# 2022-4T-MNT-2.net
KiCad netlist of a schematic drawn in EasyEDA Pro
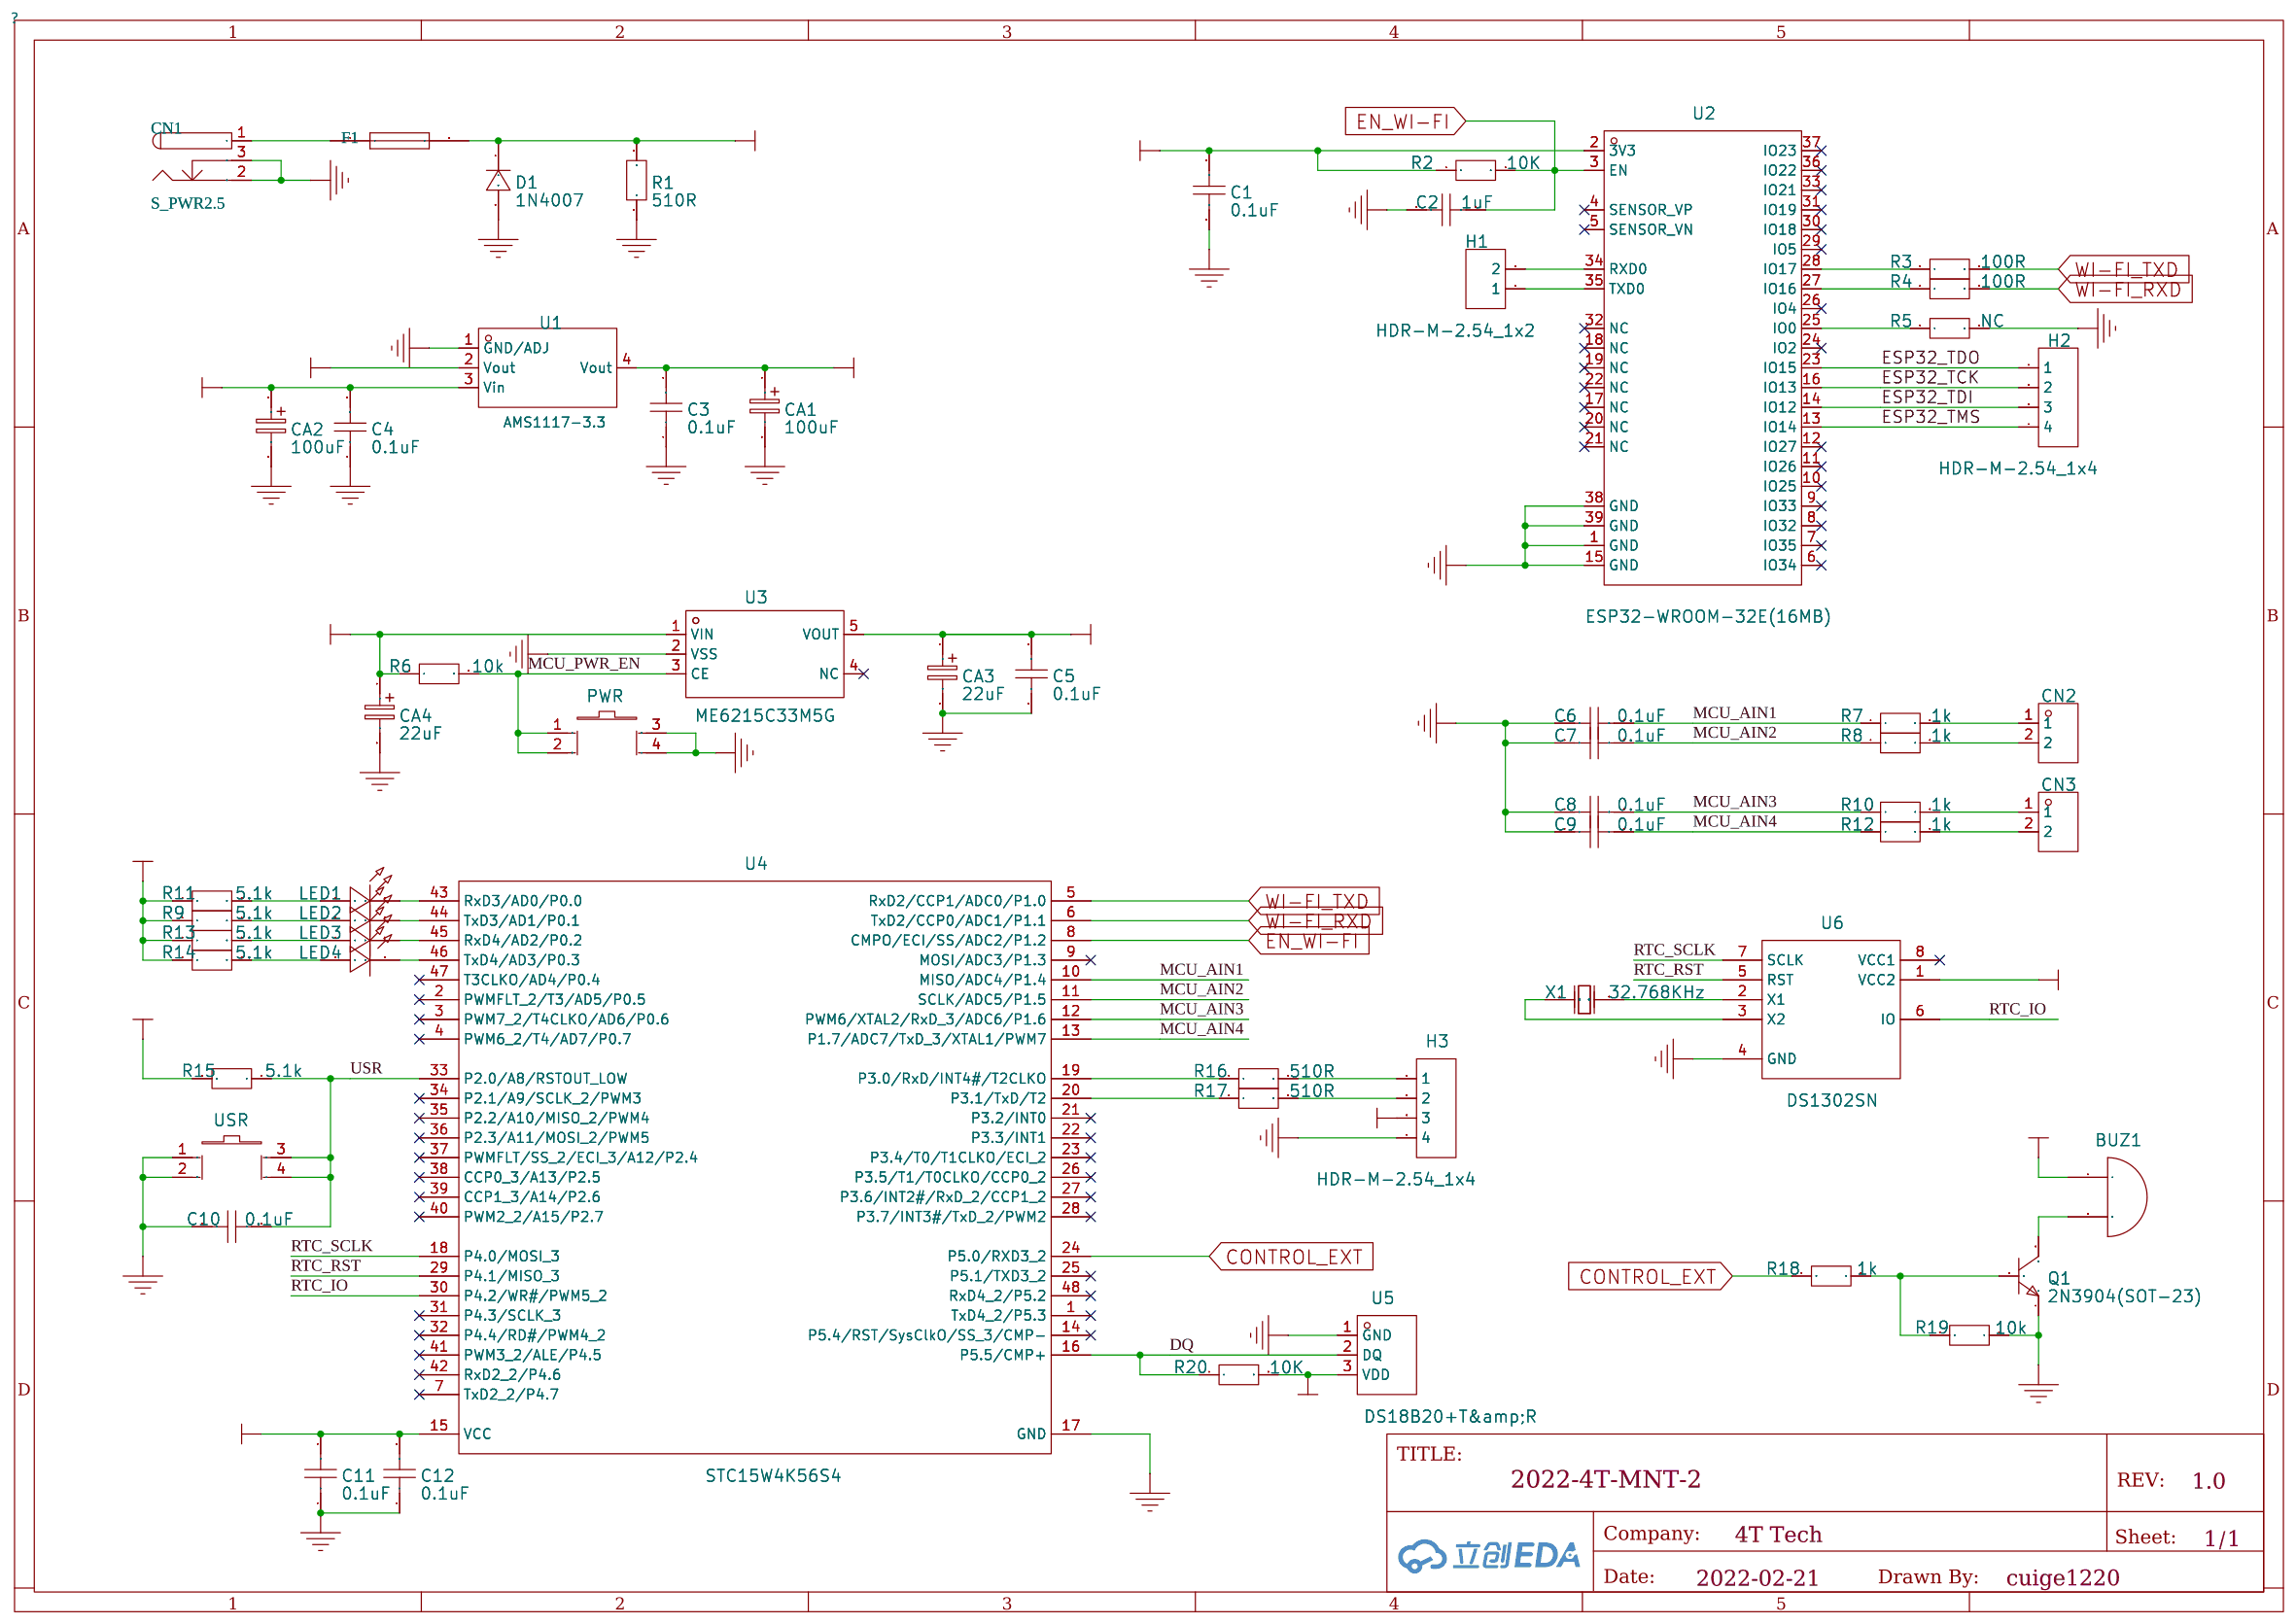
[diagram p0: schematic sheet]

(export (version "E")
  (design (tool "Eeschema 10.0.6"))
  (components
    (comp (ref "BUZ1") (value "BUZ1") (libsource (lib "easyedapro") (part "BUZ1")))
    (comp (ref "C1") (value "0.1uF") (libsource (lib "easyedapro") (part "0.1uF")))
    (comp (ref "C2") (value "1uF") (libsource (lib "easyedapro") (part "1uF")))
    (comp (ref "C3") (value "0.1uF") (libsource (lib "easyedapro") (part "0.1uF")))
    (comp (ref "C4") (value "0.1uF") (libsource (lib "easyedapro") (part "0.1uF")))
    (comp (ref "C5") (value "0.1uF") (libsource (lib "easyedapro") (part "0.1uF")))
    (comp (ref "C6") (value "0.1uF") (libsource (lib "easyedapro") (part "0.1uF")))
    (comp (ref "C7") (value "0.1uF") (libsource (lib "easyedapro") (part "0.1uF")))
    (comp (ref "C8") (value "0.1uF") (libsource (lib "easyedapro") (part "0.1uF")))
    (comp (ref "C9") (value "0.1uF") (libsource (lib "easyedapro") (part "0.1uF")))
    (comp (ref "C10") (value "0.1uF") (libsource (lib "easyedapro") (part "0.1uF")))
    (comp (ref "C11") (value "0.1uF") (libsource (lib "easyedapro") (part "0.1uF")))
    (comp (ref "C12") (value "0.1uF") (libsource (lib "easyedapro") (part "0.1uF")))
    (comp (ref "CA1") (value "100uF") (libsource (lib "easyedapro") (part "100uF")))
    (comp (ref "CA2") (value "100uF") (libsource (lib "easyedapro") (part "100uF")))
    (comp (ref "CA3") (value "22uF") (libsource (lib "easyedapro") (part "22uF")))
    (comp (ref "CA4") (value "22uF") (libsource (lib "easyedapro") (part "22uF")))
    (comp (ref "CN1") (value "S_PWR2.5") (libsource (lib "easyedapro") (part "S_PWR2.5")))
    (comp (ref "CN2")
      (value "DB128L-5.08-2P")
      (fields (field (name "Manufacturer") "DIBO"))
      (libsource (lib "easyedapro") (part "DB128L-5.08-2P"))
    )
    (comp (ref "CN3")
      (value "DB128L-5.08-2P")
      (fields (field (name "Manufacturer") "DIBO"))
      (libsource (lib "easyedapro") (part "DB128L-5.08-2P"))
    )
    (comp (ref "D1")
      (value "1N4007")
      (fields (field (name "Manufacturer") "SEMTECH"))
      (libsource (lib "easyedapro") (part "1N4007"))
    )
    (comp (ref "F1")
      (value "ASMD1210-075")
      (fields (field (name "Publisher") "Altium Limited"))
      (libsource (lib "easyedapro") (part "ASMD1210-075"))
    )
    (comp (ref "H1") (value "HDR-M-2.54_1x2") (libsource (lib "easyedapro") (part "HDR-M-2.54_1x2")))
    (comp (ref "H2") (value "HDR-M-2.54_1x4") (libsource (lib "easyedapro") (part "HDR-M-2.54_1x4")))
    (comp (ref "H3") (value "HDR-M-2.54_1x4") (libsource (lib "easyedapro") (part "HDR-M-2.54_1x4")))
    (comp (ref "LED1")
      (value "LED-TH-3mm_R")
      (fields
        (field (name "Manufacturer Part") "204-10SDRD/S530-A3-L")
        (field (name "Manufacturer") "EVERLIGHT(台湾亿光)")
      )
      (libsource (lib "easyedapro") (part "LED-TH-3mm_R"))
    )
    (comp (ref "LED2")
      (value "LED-TH-3mm_R")
      (fields
        (field (name "Manufacturer Part") "204-10SDRD/S530-A3-L")
        (field (name "Manufacturer") "EVERLIGHT(台湾亿光)")
      )
      (libsource (lib "easyedapro") (part "LED-TH-3mm_R"))
    )
    (comp (ref "LED3")
      (value "LED-TH-3mm_R")
      (fields
        (field (name "Manufacturer Part") "204-10SDRD/S530-A3-L")
        (field (name "Manufacturer") "EVERLIGHT(台湾亿光)")
      )
      (libsource (lib "easyedapro") (part "LED-TH-3mm_R"))
    )
    (comp (ref "LED4")
      (value "LED-TH-3mm_R")
      (fields
        (field (name "Manufacturer Part") "204-10SDRD/S530-A3-L")
        (field (name "Manufacturer") "EVERLIGHT(台湾亿光)")
      )
      (libsource (lib "easyedapro") (part "LED-TH-3mm_R"))
    )
    (comp (ref "PWR")
      (value "6x6x6Plastic head")
      (fields (field (name "Manufacturer") "ReliaPro"))
      (libsource (lib "easyedapro") (part "6x6x6Plastic head"))
    )
    (comp (ref "Q1")
      (value "2N3904(SOT-23)")
      (fields (field (name "Manufacturer Part") "2n3904S-RTK/PS") (field (name "Manufacturer") "KEC"))
      (libsource (lib "easyedapro") (part "2N3904(SOT-23)"))
    )
    (comp (ref "R1") (value "510R") (libsource (lib "easyedapro") (part "510R")))
    (comp (ref "R2") (value "10K") (libsource (lib "easyedapro") (part "10K")))
    (comp (ref "R3") (value "100R") (libsource (lib "easyedapro") (part "100R")))
    (comp (ref "R4") (value "100R") (libsource (lib "easyedapro") (part "100R")))
    (comp (ref "R5") (value "NC") (libsource (lib "easyedapro") (part "NC")))
    (comp (ref "R6") (value "10k") (libsource (lib "easyedapro") (part "10k")))
    (comp (ref "R7") (value "1k") (libsource (lib "easyedapro") (part "1k")))
    (comp (ref "R8") (value "1k") (libsource (lib "easyedapro") (part "1k")))
    (comp (ref "R9") (value "5.1k") (libsource (lib "easyedapro") (part "5.1k")))
    (comp (ref "R10") (value "1k") (libsource (lib "easyedapro") (part "1k")))
    (comp (ref "R11") (value "5.1k") (libsource (lib "easyedapro") (part "5.1k")))
    (comp (ref "R12") (value "1k") (libsource (lib "easyedapro") (part "1k")))
    (comp (ref "R13") (value "5.1k") (libsource (lib "easyedapro") (part "5.1k")))
    (comp (ref "R14") (value "5.1k") (libsource (lib "easyedapro") (part "5.1k")))
    (comp (ref "R15") (value "5.1k") (libsource (lib "easyedapro") (part "5.1k")))
    (comp (ref "R16") (value "510R") (libsource (lib "easyedapro") (part "510R")))
    (comp (ref "R17") (value "510R") (libsource (lib "easyedapro") (part "510R")))
    (comp (ref "R18") (value "1k") (libsource (lib "easyedapro") (part "1k")))
    (comp (ref "R19") (value "10k") (libsource (lib "easyedapro") (part "10k")))
    (comp (ref "R20") (value "10K") (libsource (lib "easyedapro") (part "10K")))
    (comp (ref "U1")
      (value "AMS1117-3.3")
      (fields (field (name "Manufacturer") "AMS"))
      (libsource (lib "easyedapro") (part "AMS1117-3.3"))
    )
    (comp (ref "U2")
      (value "ESP32-WROOM-32E(16MB)")
      (fields (field (name "Manufacturer") "Espressif Systems"))
      (libsource (lib "easyedapro") (part "ESP32-WROOM-32E(16MB)"))
    )
    (comp (ref "U3")
      (value "ME6215C33M5G")
      (fields (field (name "Manufacturer") "MICRONE"))
      (libsource (lib "easyedapro") (part "ME6215C33M5G"))
    )
    (comp (ref "U4")
      (value "STC15W4K56S4")
      (fields (field (name "Manufacturer") "STC"))
      (libsource (lib "easyedapro") (part "STC15W4K56S4"))
    )
    (comp (ref "U5")
      (value "DS18B20+T&amp;R")
      (fields (field (name "Manufacturer") "MAXIM(美信)"))
      (libsource (lib "easyedapro") (part "DS18B20+T&amp;R"))
    )
    (comp (ref "U6") (value "DS1302SN") (libsource (lib "easyedapro") (part "DS1302SN")))
    (comp (ref "USR")
      (value "6x6x6Plastic head")
      (fields (field (name "Manufacturer") "ReliaPro"))
      (libsource (lib "easyedapro") (part "6x6x6Plastic head"))
    )
    (comp (ref "X1")
      (value "32.768KHz")
      (fields (field (name "Manufacturer Part") "CFS-20632768EZFB") (field (name "Manufacturer") "CITIZEN"))
      (libsource (lib "easyedapro") (part "32.768KHz"))
    )
  )
  (nets
    (net (code "1") (name "+5V0") (class "Default")
      (node (ref "C4") (pin "2") (pinfunction "2_2") (pintype "input"))
      (node (ref "CA2") (pin "1") (pinfunction "1_1") (pintype "input"))
      (node (ref "CA4") (pin "1") (pinfunction "1_1") (pintype "input"))
      (node (ref "D1") (pin "1") (pinfunction "1_1") (pintype "input"))
      (node (ref "F1") (pin "2") (pinfunction "2_2") (pintype "input"))
      (node (ref "R1") (pin "2") (pinfunction "2_2") (pintype "input"))
      (node (ref "R6") (pin "1") (pinfunction "1_1") (pintype "input"))
      (node (ref "U1") (pin "3") (pinfunction "Vin_3") (pintype "input"))
      (node (ref "U3") (pin "1") (pinfunction "VIN_1") (pintype "input"))
    )
    (net (code "2") (name "/DQ") (class "Default")
      (node (ref "R20") (pin "1") (pinfunction "1_1") (pintype "input"))
      (node (ref "U4") (pin "16") (pinfunction "P5.5/CMP+_16") (pintype "input"))
      (node (ref "U5") (pin "2") (pinfunction "DQ_2") (pintype "input"))
    )
    (net (code "3") (name "/ESP32_TCK") (class "Default")
      (node (ref "H2") (pin "2") (pinfunction "2_2") (pintype "input"))
      (node (ref "U2") (pin "16") (pinfunction "IO13_16") (pintype "input"))
    )
    (net (code "4") (name "/ESP32_TDI") (class "Default")
      (node (ref "H2") (pin "3") (pinfunction "3_3") (pintype "input"))
      (node (ref "U2") (pin "14") (pinfunction "IO12_14") (pintype "input"))
    )
    (net (code "5") (name "/ESP32_TDO") (class "Default")
      (node (ref "H2") (pin "1") (pinfunction "1_1") (pintype "input"))
      (node (ref "U2") (pin "23") (pinfunction "IO15_23") (pintype "input"))
    )
    (net (code "6") (name "/ESP32_TMS") (class "Default")
      (node (ref "H2") (pin "4") (pinfunction "4_4") (pintype "input"))
      (node (ref "U2") (pin "13") (pinfunction "IO14_13") (pintype "input"))
    )
    (net (code "7") (name "/MCU_AIN1") (class "Default")
      (node (ref "C6") (pin "2") (pinfunction "2_2") (pintype "input"))
      (node (ref "R7") (pin "1") (pinfunction "1_1") (pintype "input"))
      (node (ref "U4") (pin "10") (pinfunction "MISO/ADC4/P1.4_10") (pintype "input"))
    )
    (net (code "8") (name "/MCU_AIN2") (class "Default")
      (node (ref "C7") (pin "2") (pinfunction "2_2") (pintype "input"))
      (node (ref "R8") (pin "1") (pinfunction "1_1") (pintype "input"))
      (node (ref "U4") (pin "11") (pinfunction "SCLK/ADC5/P1.5_11") (pintype "input"))
    )
    (net (code "9") (name "/MCU_AIN3") (class "Default")
      (node (ref "C8") (pin "2") (pinfunction "2_2") (pintype "input"))
      (node (ref "R10") (pin "1") (pinfunction "1_1") (pintype "input"))
      (node (ref "U4") (pin "12") (pinfunction "PWM6/XTAL2/RxD_3/ADC6/P1.6_12") (pintype "input"))
    )
    (net (code "10") (name "/MCU_AIN4") (class "Default")
      (node (ref "C9") (pin "2") (pinfunction "2_2") (pintype "input"))
      (node (ref "R12") (pin "1") (pinfunction "1_1") (pintype "input"))
      (node (ref "U4") (pin "13") (pinfunction "P1.7/ADC7/TxD_3/XTAL1/PWM7_13") (pintype "input"))
    )
    (net (code "11") (name "/MCU_PWR_EN") (class "Default")
      (node (ref "PWR") (pin "1") (pinfunction "1_1") (pintype "input"))
      (node (ref "PWR") (pin "2") (pinfunction "2_2") (pintype "input"))
      (node (ref "R6") (pin "2") (pinfunction "2_2") (pintype "input"))
      (node (ref "U3") (pin "3") (pinfunction "CE_3") (pintype "input"))
    )
    (net (code "12") (name "/RTC_IO") (class "Default")
      (node (ref "U4") (pin "30") (pinfunction "P4.2/WR#/PWM5_2_30") (pintype "input"))
      (node (ref "U6") (pin "6") (pinfunction "IO_6") (pintype "bidirectional"))
    )
    (net (code "13") (name "/RTC_RST") (class "Default")
      (node (ref "U4") (pin "29") (pinfunction "P4.1/MISO_3_29") (pintype "input"))
      (node (ref "U6") (pin "5") (pinfunction "RST_5") (pintype "input"))
    )
    (net (code "14") (name "/RTC_SCLK") (class "Default")
      (node (ref "U4") (pin "18") (pinfunction "P4.0/MOSI_3_18") (pintype "input"))
      (node (ref "U6") (pin "7") (pinfunction "SCLK_7") (pintype "input"))
    )
    (net (code "15") (name "/USR") (class "Default")
      (node (ref "C10") (pin "1") (pinfunction "1_1") (pintype "input"))
      (node (ref "R15") (pin "1") (pinfunction "1_1") (pintype "input"))
      (node (ref "U4") (pin "33") (pinfunction "P2.0/A8/RSTOUT_LOW_33") (pintype "input"))
      (node (ref "USR") (pin "3") (pinfunction "3_3") (pintype "input"))
      (node (ref "USR") (pin "4") (pinfunction "4_4") (pintype "input"))
    )
    (net (code "16") (name "3.3V_MCU") (class "Default")
      (node (ref "BUZ1") (pin "1") (pinfunction "A_1") (pintype "input"))
      (node (ref "C11") (pin "2") (pinfunction "2_2") (pintype "input"))
      (node (ref "C12") (pin "2") (pinfunction "2_2") (pintype "input"))
      (node (ref "C5") (pin "2") (pinfunction "2_2") (pintype "input"))
      (node (ref "CA3") (pin "1") (pinfunction "1_1") (pintype "input"))
      (node (ref "H3") (pin "3") (pinfunction "3_3") (pintype "input"))
      (node (ref "R11") (pin "1") (pinfunction "1_1") (pintype "input"))
      (node (ref "R13") (pin "1") (pinfunction "1_1") (pintype "input"))
      (node (ref "R14") (pin "1") (pinfunction "1_1") (pintype "input"))
      (node (ref "R15") (pin "2") (pinfunction "2_2") (pintype "input"))
      (node (ref "R20") (pin "2") (pinfunction "2_2") (pintype "input"))
      (node (ref "R9") (pin "1") (pinfunction "1_1") (pintype "input"))
      (node (ref "U3") (pin "5") (pinfunction "VOUT_5") (pintype "input"))
      (node (ref "U4") (pin "15") (pinfunction "VCC_15") (pintype "input"))
      (node (ref "U5") (pin "3") (pinfunction "VDD_3") (pintype "input"))
      (node (ref "U6") (pin "1") (pinfunction "VCC2_1") (pintype "input"))
    )
    (net (code "17") (name "3.3V_WIFI") (class "Default")
      (node (ref "C1") (pin "2") (pinfunction "2_2") (pintype "input"))
      (node (ref "C3") (pin "2") (pinfunction "2_2") (pintype "input"))
      (node (ref "CA1") (pin "1") (pinfunction "1_1") (pintype "input"))
      (node (ref "R2") (pin "1") (pinfunction "1_1") (pintype "input"))
      (node (ref "U1") (pin "2") (pinfunction "Vout_2") (pintype "input"))
      (node (ref "U1") (pin "4") (pinfunction "Vout_4") (pintype "input"))
      (node (ref "U2") (pin "2") (pinfunction "3V3_2") (pintype "input"))
    )
    (net (code "18") (name "CONTROL_EXT") (class "Default")
      (node (ref "R18") (pin "2") (pinfunction "2_2") (pintype "input"))
      (node (ref "U4") (pin "24") (pinfunction "P5.0/RXD3_2_24") (pintype "input"))
    )
    (net (code "19") (name "EN_WI-FI") (class "Default")
      (node (ref "C2") (pin "1") (pinfunction "1_1") (pintype "input"))
      (node (ref "R2") (pin "2") (pinfunction "2_2") (pintype "input"))
      (node (ref "U2") (pin "3") (pinfunction "EN_3") (pintype "input"))
      (node (ref "U4") (pin "8") (pinfunction "CMPO/ECI/SS/ADC2/P1.2_8") (pintype "input"))
    )
    (net (code "20") (name "GND") (class "Default")
      (node (ref "C1") (pin "1") (pinfunction "1_1") (pintype "input"))
      (node (ref "C10") (pin "2") (pinfunction "2_2") (pintype "input"))
      (node (ref "C11") (pin "1") (pinfunction "1_1") (pintype "input"))
      (node (ref "C12") (pin "1") (pinfunction "1_1") (pintype "input"))
      (node (ref "C2") (pin "2") (pinfunction "2_2") (pintype "input"))
      (node (ref "C3") (pin "1") (pinfunction "1_1") (pintype "input"))
      (node (ref "C4") (pin "1") (pinfunction "1_1") (pintype "input"))
      (node (ref "C5") (pin "1") (pinfunction "1_1") (pintype "input"))
      (node (ref "C6") (pin "1") (pinfunction "1_1") (pintype "input"))
      (node (ref "C7") (pin "1") (pinfunction "1_1") (pintype "input"))
      (node (ref "C8") (pin "1") (pinfunction "1_1") (pintype "input"))
      (node (ref "C9") (pin "1") (pinfunction "1_1") (pintype "input"))
      (node (ref "CA1") (pin "2") (pinfunction "2_2") (pintype "input"))
      (node (ref "CA2") (pin "2") (pinfunction "2_2") (pintype "input"))
      (node (ref "CA3") (pin "2") (pinfunction "2_2") (pintype "input"))
      (node (ref "CA4") (pin "2") (pinfunction "2_2") (pintype "input"))
      (node (ref "CN1") (pin "2") (pinfunction "2_2") (pintype "input"))
      (node (ref "CN1") (pin "3") (pinfunction "3_3") (pintype "input"))
      (node (ref "D1") (pin "2") (pinfunction "2_2") (pintype "input"))
      (node (ref "H3") (pin "4") (pinfunction "4_4") (pintype "input"))
      (node (ref "PWR") (pin "3") (pinfunction "3_3") (pintype "input"))
      (node (ref "PWR") (pin "4") (pinfunction "4_4") (pintype "input"))
      (node (ref "Q1") (pin "1") (pinfunction "E_1") (pintype "input"))
      (node (ref "R1") (pin "1") (pinfunction "1_1") (pintype "input"))
      (node (ref "R19") (pin "1") (pinfunction "1_1") (pintype "input"))
      (node (ref "R5") (pin "2") (pinfunction "2_2") (pintype "input"))
      (node (ref "U1") (pin "1") (pinfunction "GND/ADJ_1") (pintype "input"))
      (node (ref "U2") (pin "1") (pinfunction "GND_1") (pintype "input"))
      (node (ref "U2") (pin "15") (pinfunction "GND_15") (pintype "input"))
      (node (ref "U2") (pin "38") (pinfunction "GND_38") (pintype "input"))
      (node (ref "U2") (pin "39") (pinfunction "GND_39") (pintype "input"))
      (node (ref "U3") (pin "2") (pinfunction "VSS_2") (pintype "input"))
      (node (ref "U4") (pin "17") (pinfunction "GND_17") (pintype "input"))
      (node (ref "U5") (pin "1") (pinfunction "GND_1") (pintype "input"))
      (node (ref "U6") (pin "4") (pinfunction "GND_4") (pintype "input"))
      (node (ref "USR") (pin "1") (pinfunction "1_1") (pintype "input"))
      (node (ref "USR") (pin "2") (pinfunction "2_2") (pintype "input"))
    )
    (net (code "21") (name "Net-(BUZ1-B)") (class "Default")
      (node (ref "BUZ1") (pin "2") (pinfunction "B_2") (pintype "input"))
      (node (ref "Q1") (pin "3") (pinfunction "C_3") (pintype "input"))
    )
    (net (code "22") (name "Net-(CN1-Pad1)") (class "Default")
      (node (ref "CN1") (pin "1") (pinfunction "1_1") (pintype "input"))
      (node (ref "F1") (pin "1") (pinfunction "1_1") (pintype "input"))
    )
    (net (code "23") (name "Net-(CN2-Pad1)") (class "Default")
      (node (ref "CN2") (pin "1") (pinfunction "1_1") (pintype "input"))
      (node (ref "R7") (pin "2") (pinfunction "2_2") (pintype "input"))
    )
    (net (code "24") (name "Net-(CN2-Pad2)") (class "Default")
      (node (ref "CN2") (pin "2") (pinfunction "2_2") (pintype "input"))
      (node (ref "R8") (pin "2") (pinfunction "2_2") (pintype "input"))
    )
    (net (code "25") (name "Net-(CN3-Pad1)") (class "Default")
      (node (ref "CN3") (pin "1") (pinfunction "1_1") (pintype "input"))
      (node (ref "R10") (pin "2") (pinfunction "2_2") (pintype "input"))
    )
    (net (code "26") (name "Net-(CN3-Pad2)") (class "Default")
      (node (ref "CN3") (pin "2") (pinfunction "2_2") (pintype "input"))
      (node (ref "R12") (pin "2") (pinfunction "2_2") (pintype "input"))
    )
    (net (code "27") (name "Net-(H3-Pad1)") (class "Default")
      (node (ref "H3") (pin "1") (pinfunction "1_1") (pintype "input"))
      (node (ref "R16") (pin "2") (pinfunction "2_2") (pintype "input"))
    )
    (net (code "28") (name "Net-(H3-Pad2)") (class "Default")
      (node (ref "H3") (pin "2") (pinfunction "2_2") (pintype "input"))
      (node (ref "R17") (pin "2") (pinfunction "2_2") (pintype "input"))
    )
    (net (code "29") (name "Net-(LED1-Pad1)") (class "Default")
      (node (ref "LED1") (pin "1") (pinfunction "1_1") (pintype "input"))
      (node (ref "R9") (pin "2") (pinfunction "2_2") (pintype "input"))
    )
    (net (code "30") (name "Net-(LED2-Pad1)") (class "Default")
      (node (ref "LED2") (pin "1") (pinfunction "1_1") (pintype "input"))
      (node (ref "R11") (pin "2") (pinfunction "2_2") (pintype "input"))
    )
    (net (code "31") (name "Net-(LED3-Pad1)") (class "Default")
      (node (ref "LED3") (pin "1") (pinfunction "1_1") (pintype "input"))
      (node (ref "R13") (pin "2") (pinfunction "2_2") (pintype "input"))
    )
    (net (code "32") (name "Net-(LED4-Pad1)") (class "Default")
      (node (ref "LED4") (pin "1") (pinfunction "1_1") (pintype "input"))
      (node (ref "R14") (pin "2") (pinfunction "2_2") (pintype "input"))
    )
    (net (code "33") (name "Net-(Q1-B)") (class "Default")
      (node (ref "Q1") (pin "2") (pinfunction "B_2") (pintype "input"))
      (node (ref "R18") (pin "1") (pinfunction "1_1") (pintype "input"))
      (node (ref "R19") (pin "2") (pinfunction "2_2") (pintype "input"))
    )
    (net (code "34") (name "Net-(U2-IO0)") (class "Default")
      (node (ref "R5") (pin "1") (pinfunction "1_1") (pintype "input"))
      (node (ref "U2") (pin "25") (pinfunction "IO0_25") (pintype "input"))
    )
    (net (code "35") (name "Net-(U2-IO16)") (class "Default")
      (node (ref "R4") (pin "1") (pinfunction "1_1") (pintype "input"))
      (node (ref "U2") (pin "27") (pinfunction "IO16_27") (pintype "input"))
    )
    (net (code "36") (name "Net-(U2-IO17)") (class "Default")
      (node (ref "R3") (pin "1") (pinfunction "1_1") (pintype "input"))
      (node (ref "U2") (pin "28") (pinfunction "IO17_28") (pintype "input"))
    )
    (net (code "37") (name "Net-(U2-RXD0)") (class "Default")
      (node (ref "H1") (pin "2") (pinfunction "2_2") (pintype "input"))
      (node (ref "U2") (pin "34") (pinfunction "RXD0_34") (pintype "input"))
    )
    (net (code "38") (name "Net-(U2-TXD0)") (class "Default")
      (node (ref "H1") (pin "1") (pinfunction "1_1") (pintype "input"))
      (node (ref "U2") (pin "35") (pinfunction "TXD0_35") (pintype "input"))
    )
    (net (code "39") (name "Net-(U4-P3.0{slash}RxD{slash}INT4#{slash}T2CLKO)") (class "Default")
      (node (ref "R16") (pin "1") (pinfunction "1_1") (pintype "input"))
      (node (ref "U4") (pin "19") (pinfunction "P3.0/RxD/INT4#/T2CLKO_19") (pintype "input"))
    )
    (net (code "40") (name "Net-(U4-P3.1{slash}TxD{slash}T2)") (class "Default")
      (node (ref "R17") (pin "1") (pinfunction "1_1") (pintype "input"))
      (node (ref "U4") (pin "20") (pinfunction "P3.1/TxD/T2_20") (pintype "input"))
    )
    (net (code "41") (name "Net-(U4-RxD3{slash}AD0{slash}P0.0)") (class "Default")
      (node (ref "LED1") (pin "2") (pinfunction "2_2") (pintype "input"))
      (node (ref "U4") (pin "43") (pinfunction "RxD3/AD0/P0.0_43") (pintype "input"))
    )
    (net (code "42") (name "Net-(U4-RxD4{slash}AD2{slash}P0.2)") (class "Default")
      (node (ref "LED3") (pin "2") (pinfunction "2_2") (pintype "input"))
      (node (ref "U4") (pin "45") (pinfunction "RxD4/AD2/P0.2_45") (pintype "input"))
    )
    (net (code "43") (name "Net-(U4-TxD3{slash}AD1{slash}P0.1)") (class "Default")
      (node (ref "LED2") (pin "2") (pinfunction "2_2") (pintype "input"))
      (node (ref "U4") (pin "44") (pinfunction "TxD3/AD1/P0.1_44") (pintype "input"))
    )
    (net (code "44") (name "Net-(U4-TxD4{slash}AD3{slash}P0.3)") (class "Default")
      (node (ref "LED4") (pin "2") (pinfunction "2_2") (pintype "input"))
      (node (ref "U4") (pin "46") (pinfunction "TxD4/AD3/P0.3_46") (pintype "input"))
    )
    (net (code "45") (name "Net-(U6-X1)") (class "Default")
      (node (ref "U6") (pin "2") (pinfunction "X1_2") (pintype "input"))
      (node (ref "X1") (pin "2") (pinfunction "OSC2_2") (pintype "input"))
    )
    (net (code "46") (name "Net-(U6-X2)") (class "Default")
      (node (ref "U6") (pin "3") (pinfunction "X2_3") (pintype "input"))
      (node (ref "X1") (pin "1") (pinfunction "OSC1_1") (pintype "input"))
    )
    (net (code "47") (name "WI-FI_RXD") (class "Default")
      (node (ref "R4") (pin "2") (pinfunction "2_2") (pintype "input"))
      (node (ref "U4") (pin "6") (pinfunction "TxD2/CCP0/ADC1/P1.1_6") (pintype "input"))
    )
    (net (code "48") (name "WI-FI_TXD") (class "Default")
      (node (ref "R3") (pin "2") (pinfunction "2_2") (pintype "input"))
      (node (ref "U4") (pin "5") (pinfunction "RxD2/CCP1/ADC0/P1.0_5") (pintype "input"))
    )
    (net (code "49") (name "unconnected-(U2-IO2-Pad24)") (class "Default")
      (node (ref "U2") (pin "24") (pinfunction "IO2_24") (pintype "input+no_connect"))
    )
    (net (code "50") (name "unconnected-(U2-IO4-Pad26)") (class "Default")
      (node (ref "U2") (pin "26") (pinfunction "IO4_26") (pintype "input+no_connect"))
    )
    (net (code "51") (name "unconnected-(U2-IO5-Pad29)") (class "Default")
      (node (ref "U2") (pin "29") (pinfunction "IO5_29") (pintype "input+no_connect"))
    )
    (net (code "52") (name "unconnected-(U2-IO18-Pad30)") (class "Default")
      (node (ref "U2") (pin "30") (pinfunction "IO18_30") (pintype "input+no_connect"))
    )
    (net (code "53") (name "unconnected-(U2-IO19-Pad31)") (class "Default")
      (node (ref "U2") (pin "31") (pinfunction "IO19_31") (pintype "input+no_connect"))
    )
    (net (code "54") (name "unconnected-(U2-IO21-Pad33)") (class "Default")
      (node (ref "U2") (pin "33") (pinfunction "IO21_33") (pintype "input+no_connect"))
    )
    (net (code "55") (name "unconnected-(U2-IO22-Pad36)") (class "Default")
      (node (ref "U2") (pin "36") (pinfunction "IO22_36") (pintype "input+no_connect"))
    )
    (net (code "56") (name "unconnected-(U2-IO23-Pad37)") (class "Default")
      (node (ref "U2") (pin "37") (pinfunction "IO23_37") (pintype "input+no_connect"))
    )
    (net (code "57") (name "unconnected-(U2-IO25-Pad10)") (class "Default")
      (node (ref "U2") (pin "10") (pinfunction "IO25_10") (pintype "input+no_connect"))
    )
    (net (code "58") (name "unconnected-(U2-IO26-Pad11)") (class "Default")
      (node (ref "U2") (pin "11") (pinfunction "IO26_11") (pintype "input+no_connect"))
    )
    (net (code "59") (name "unconnected-(U2-IO27-Pad12)") (class "Default")
      (node (ref "U2") (pin "12") (pinfunction "IO27_12") (pintype "input+no_connect"))
    )
    (net (code "60") (name "unconnected-(U2-IO32-Pad8)") (class "Default")
      (node (ref "U2") (pin "8") (pinfunction "IO32_8") (pintype "input+no_connect"))
    )
    (net (code "61") (name "unconnected-(U2-IO33-Pad9)") (class "Default")
      (node (ref "U2") (pin "9") (pinfunction "IO33_9") (pintype "input+no_connect"))
    )
    (net (code "62") (name "unconnected-(U2-IO34-Pad6)") (class "Default")
      (node (ref "U2") (pin "6") (pinfunction "IO34_6") (pintype "input+no_connect"))
    )
    (net (code "63") (name "unconnected-(U2-IO35-Pad7)") (class "Default")
      (node (ref "U2") (pin "7") (pinfunction "IO35_7") (pintype "input+no_connect"))
    )
    (net (code "64") (name "unconnected-(U2-NC-Pad17)") (class "Default")
      (node (ref "U2") (pin "17") (pinfunction "NC_17") (pintype "input+no_connect"))
    )
    (net (code "65") (name "unconnected-(U2-NC-Pad18)") (class "Default")
      (node (ref "U2") (pin "18") (pinfunction "NC_18") (pintype "input+no_connect"))
    )
    (net (code "66") (name "unconnected-(U2-NC-Pad19)") (class "Default")
      (node (ref "U2") (pin "19") (pinfunction "NC_19") (pintype "input+no_connect"))
    )
    (net (code "67") (name "unconnected-(U2-NC-Pad20)") (class "Default")
      (node (ref "U2") (pin "20") (pinfunction "NC_20") (pintype "input+no_connect"))
    )
    (net (code "68") (name "unconnected-(U2-NC-Pad21)") (class "Default")
      (node (ref "U2") (pin "21") (pinfunction "NC_21") (pintype "input+no_connect"))
    )
    (net (code "69") (name "unconnected-(U2-NC-Pad22)") (class "Default")
      (node (ref "U2") (pin "22") (pinfunction "NC_22") (pintype "input+no_connect"))
    )
    (net (code "70") (name "unconnected-(U2-NC-Pad32)") (class "Default")
      (node (ref "U2") (pin "32") (pinfunction "NC_32") (pintype "input+no_connect"))
    )
    (net (code "71") (name "unconnected-(U2-SENSOR_VN-Pad5)") (class "Default")
      (node (ref "U2") (pin "5") (pinfunction "SENSOR_VN_5") (pintype "input+no_connect"))
    )
    (net (code "72") (name "unconnected-(U2-SENSOR_VP-Pad4)") (class "Default")
      (node (ref "U2") (pin "4") (pinfunction "SENSOR_VP_4") (pintype "input+no_connect"))
    )
    (net (code "73") (name "unconnected-(U3-NC-Pad4)") (class "Default")
      (node (ref "U3") (pin "4") (pinfunction "NC_4") (pintype "input+no_connect"))
    )
    (net (code "74") (name "unconnected-(U4-CCP0_3{slash}A13{slash}P2.5-Pad38)") (class "Default")
      (node (ref "U4") (pin "38") (pinfunction "CCP0_3/A13/P2.5_38") (pintype "input+no_connect"))
    )
    (net (code "75") (name "unconnected-(U4-CCP1_3{slash}A14{slash}P2.6-Pad39)") (class "Default")
      (node (ref "U4") (pin "39") (pinfunction "CCP1_3/A14/P2.6_39") (pintype "input+no_connect"))
    )
    (net (code "76") (name "unconnected-(U4-MOSI{slash}ADC3{slash}P1.3-Pad9)") (class "Default")
      (node (ref "U4") (pin "9") (pinfunction "MOSI/ADC3/P1.3_9") (pintype "input+no_connect"))
    )
    (net (code "77") (name "unconnected-(U4-P2.1{slash}A9{slash}SCLK_2{slash}PWM3-Pad34)") (class "Default")
      (node (ref "U4") (pin "34") (pinfunction "P2.1/A9/SCLK_2/PWM3_34") (pintype "input+no_connect"))
    )
    (net (code "78") (name "unconnected-(U4-P2.2{slash}A10{slash}MISO_2{slash}PWM4-Pad35)") (class "Default")
      (node (ref "U4") (pin "35") (pinfunction "P2.2/A10/MISO_2/PWM4_35") (pintype "input+no_connect"))
    )
    (net (code "79") (name "unconnected-(U4-P2.3{slash}A11{slash}MOSI_2{slash}PWM5-Pad36)") (class "Default")
      (node (ref "U4") (pin "36") (pinfunction "P2.3/A11/MOSI_2/PWM5_36") (pintype "input+no_connect"))
    )
    (net (code "80") (name "unconnected-(U4-P3.2{slash}INT0-Pad21)") (class "Default")
      (node (ref "U4") (pin "21") (pinfunction "P3.2/INT0_21") (pintype "input+no_connect"))
    )
    (net (code "81") (name "unconnected-(U4-P3.3{slash}INT1-Pad22)") (class "Default")
      (node (ref "U4") (pin "22") (pinfunction "P3.3/INT1_22") (pintype "input+no_connect"))
    )
    (net (code "82") (name "unconnected-(U4-P3.4{slash}T0{slash}T1CLKO{slash}ECI_2-Pad23)") (class "Default")
      (node (ref "U4") (pin "23") (pinfunction "P3.4/T0/T1CLKO/ECI_2_23") (pintype "input+no_connect"))
    )
    (net (code "83") (name "unconnected-(U4-P3.5{slash}T1{slash}T0CLKO{slash}CCP0_2-Pad26)") (class "Default")
      (node (ref "U4") (pin "26") (pinfunction "P3.5/T1/T0CLKO/CCP0_2_26") (pintype "input+no_connect"))
    )
    (net (code "84") (name "unconnected-(U4-P3.6{slash}INT2#{slash}RxD_2{slash}CCP1_2-Pad27)") (class "Default")
      (node (ref "U4") (pin "27") (pinfunction "P3.6/INT2#/RxD_2/CCP1_2_27") (pintype "input+no_connect"))
    )
    (net (code "85") (name "unconnected-(U4-P3.7{slash}INT3#{slash}TxD_2{slash}PWM2-Pad28)") (class "Default")
      (node (ref "U4") (pin "28") (pinfunction "P3.7/INT3#/TxD_2/PWM2_28") (pintype "input+no_connect"))
    )
    (net (code "86") (name "unconnected-(U4-P4.3{slash}SCLK_3-Pad31)") (class "Default")
      (node (ref "U4") (pin "31") (pinfunction "P4.3/SCLK_3_31") (pintype "input+no_connect"))
    )
    (net (code "87") (name "unconnected-(U4-P4.4{slash}RD#{slash}PWM4_2-Pad32)") (class "Default")
      (node (ref "U4") (pin "32") (pinfunction "P4.4/RD#/PWM4_2_32") (pintype "input+no_connect"))
    )
    (net (code "88") (name "unconnected-(U4-P5.1{slash}TXD3_2-Pad25)") (class "Default")
      (node (ref "U4") (pin "25") (pinfunction "P5.1/TXD3_2_25") (pintype "input+no_connect"))
    )
    (net (code "89") (name "unconnected-(U4-P5.4{slash}RST{slash}SysClkO{slash}SS_3{slash}CMP--Pad14)") (class "Default")
      (node (ref "U4") (pin "14") (pinfunction "P5.4/RST/SysClkO/SS_3/CMP-_14") (pintype "input+no_connect"))
    )
    (net (code "90") (name "unconnected-(U4-PWM2_2{slash}A15{slash}P2.7-Pad40)") (class "Default")
      (node (ref "U4") (pin "40") (pinfunction "PWM2_2/A15/P2.7_40") (pintype "input+no_connect"))
    )
    (net (code "91") (name "unconnected-(U4-PWM3_2{slash}ALE{slash}P4.5-Pad41)") (class "Default")
      (node (ref "U4") (pin "41") (pinfunction "PWM3_2/ALE/P4.5_41") (pintype "input+no_connect"))
    )
    (net (code "92") (name "unconnected-(U4-PWM6_2{slash}T4{slash}AD7{slash}P0.7-Pad4)") (class "Default")
      (node (ref "U4") (pin "4") (pinfunction "PWM6_2/T4/AD7/P0.7_4") (pintype "input+no_connect"))
    )
    (net (code "93") (name "unconnected-(U4-PWM7_2{slash}T4CLKO{slash}AD6{slash}P0.6-Pad3)") (class "Default")
      (node (ref "U4") (pin "3") (pinfunction "PWM7_2/T4CLKO/AD6/P0.6_3") (pintype "input+no_connect"))
    )
    (net (code "94") (name "unconnected-(U4-PWMFLT_2{slash}T3{slash}AD5{slash}P0.5-Pad2)") (class "Default")
      (node (ref "U4") (pin "2") (pinfunction "PWMFLT_2/T3/AD5/P0.5_2") (pintype "input+no_connect"))
    )
    (net (code "95") (name "unconnected-(U4-PWMFLT{slash}SS_2{slash}ECI_3{slash}A12{slash}P2.4-Pad37)") (class "Default")
      (node (ref "U4") (pin "37") (pinfunction "PWMFLT/SS_2/ECI_3/A12/P2.4_37") (pintype "input+no_connect"))
    )
    (net (code "96") (name "unconnected-(U4-RxD2_2{slash}P4.6-Pad42)") (class "Default")
      (node (ref "U4") (pin "42") (pinfunction "RxD2_2/P4.6_42") (pintype "input+no_connect"))
    )
    (net (code "97") (name "unconnected-(U4-RxD4_2{slash}P5.2-Pad48)") (class "Default")
      (node (ref "U4") (pin "48") (pinfunction "RxD4_2/P5.2_48") (pintype "input+no_connect"))
    )
    (net (code "98") (name "unconnected-(U4-T3CLKO{slash}AD4{slash}P0.4-Pad47)") (class "Default")
      (node (ref "U4") (pin "47") (pinfunction "T3CLKO/AD4/P0.4_47") (pintype "input+no_connect"))
    )
    (net (code "99") (name "unconnected-(U4-TxD2_2{slash}P4.7-Pad7)") (class "Default")
      (node (ref "U4") (pin "7") (pinfunction "TxD2_2/P4.7_7") (pintype "input+no_connect"))
    )
    (net (code "100") (name "unconnected-(U4-TxD4_2{slash}P5.3-Pad1)") (class "Default")
      (node (ref "U4") (pin "1") (pinfunction "TxD4_2/P5.3_1") (pintype "input+no_connect"))
    )
    (net (code "101") (name "unconnected-(U6-VCC1-Pad8)") (class "Default")
      (node (ref "U6") (pin "8") (pinfunction "VCC1_8") (pintype "input+no_connect"))
    )
  )
)
